# Touch_Drum_V1_Simple.net
KiCad netlist of a schematic drawn in EAGLE
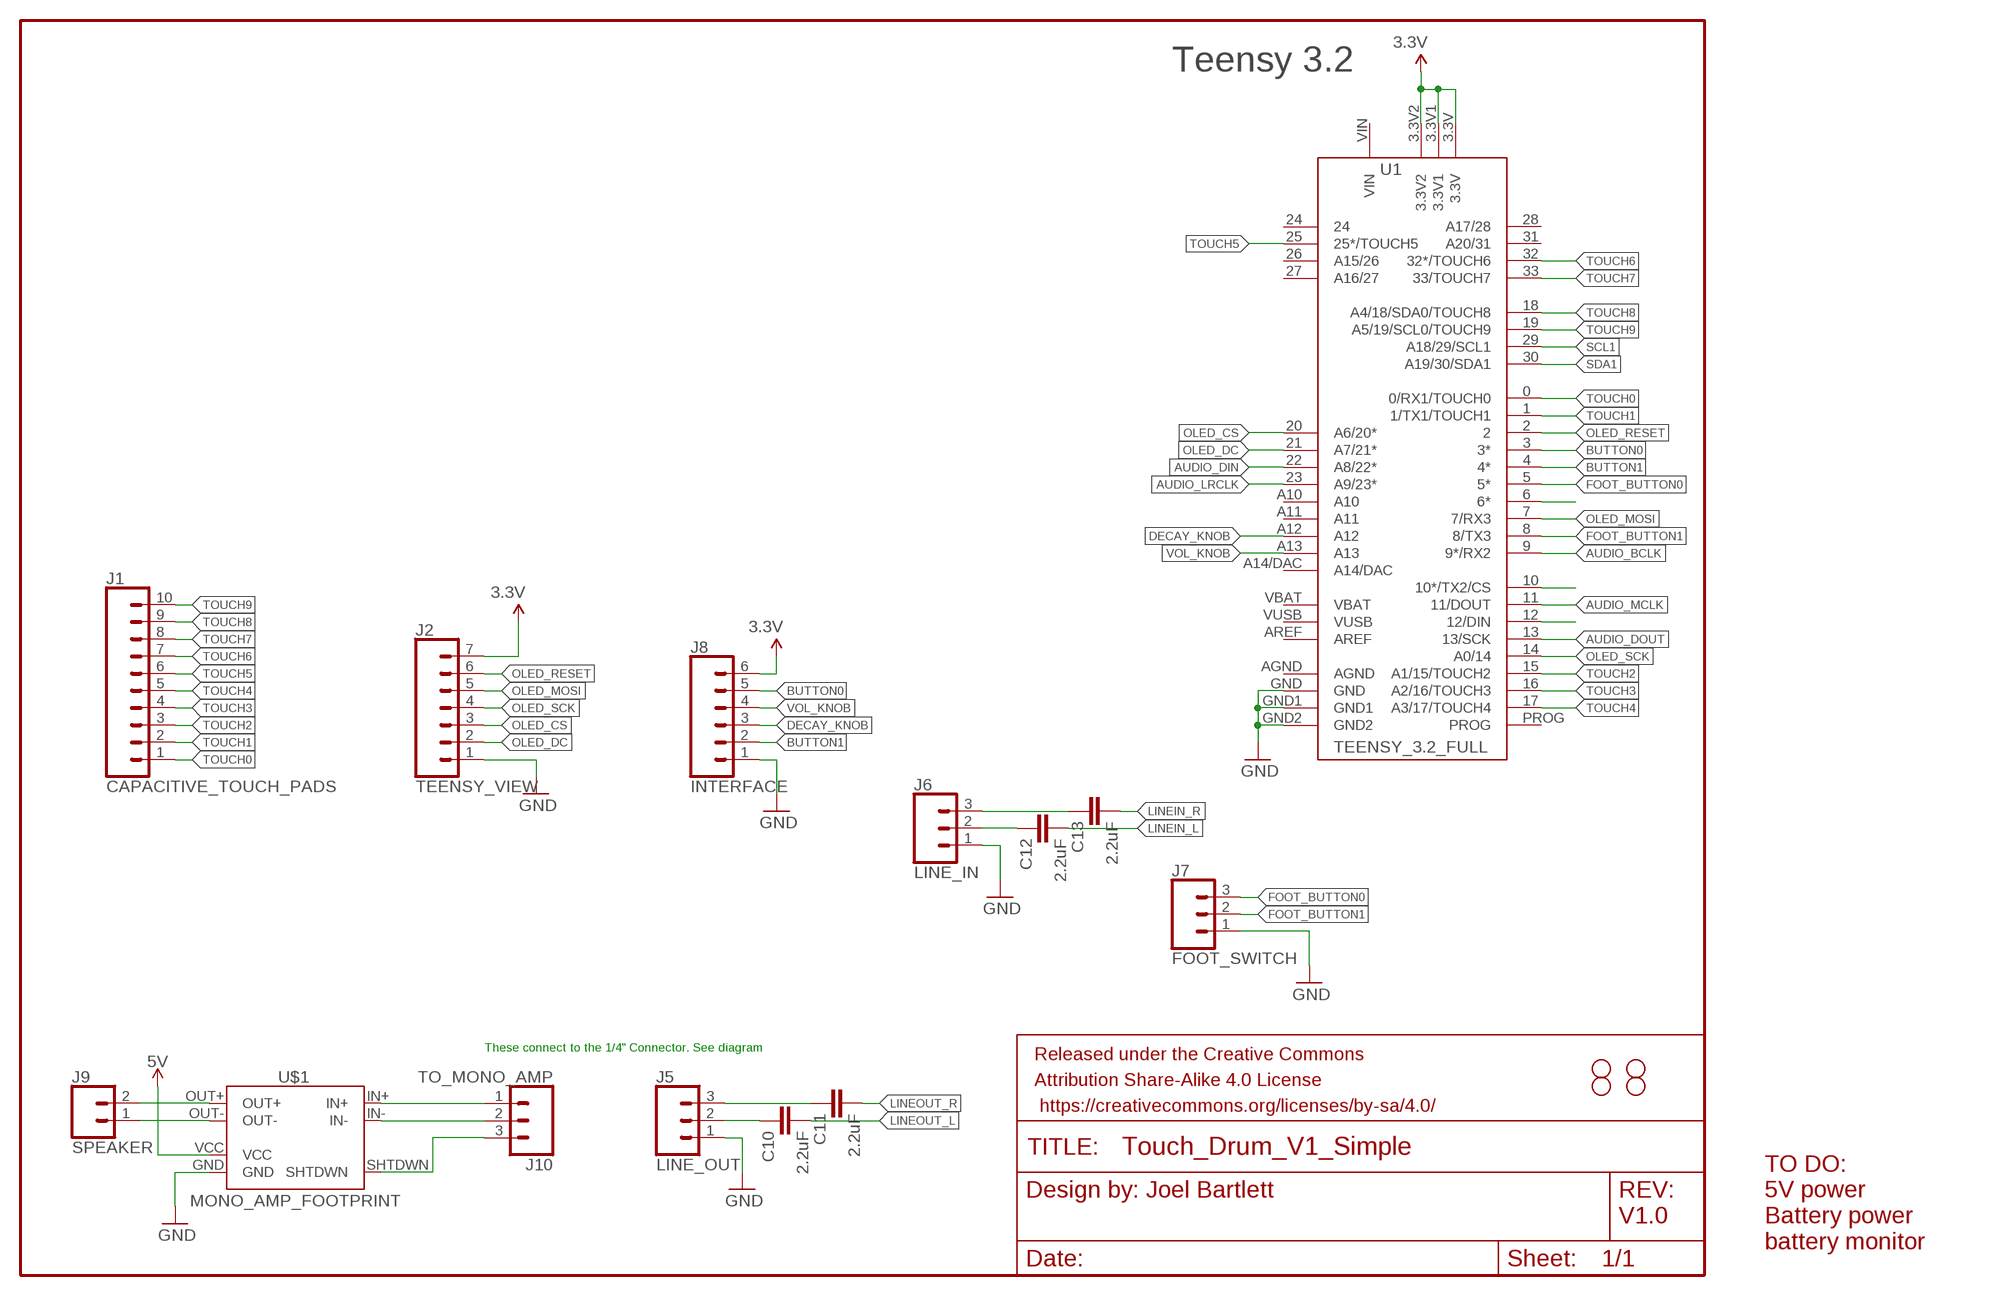
[diagram p0: schematic, sheet 1]

(export (version "E")
  (design (tool "Eeschema 10.0.6"))
  (components
    (comp (ref "C10")
      (value "2.2uF")
      (footprint "eagle-import:0603")
      (libsource (lib "eagle-import") (part "2.2UF-0603-10V-20%"))
    )
    (comp (ref "C11")
      (value "2.2uF")
      (footprint "eagle-import:0603")
      (libsource (lib "eagle-import") (part "2.2UF-0603-10V-20%"))
    )
    (comp (ref "C12")
      (value "2.2uF")
      (footprint "eagle-import:0603")
      (libsource (lib "eagle-import") (part "2.2UF-0603-10V-20%"))
    )
    (comp (ref "C13")
      (value "2.2uF")
      (footprint "eagle-import:0603")
      (libsource (lib "eagle-import") (part "2.2UF-0603-10V-20%"))
    )
    (comp (ref "FRAME1")
      (value "FRAME-LETTER")
      (footprint "eagle-import:CREATIVE_COMMONS")
      (libsource (lib "eagle-import") (part "FRAME-LETTER"))
    )
    (comp (ref "H1")
      (value "STAND-OFF")
      (footprint "eagle-import:STAND-OFF")
      (libsource (lib "eagle-import") (part "STAND-OFF"))
    )
    (comp (ref "H2")
      (value "STAND-OFF")
      (footprint "eagle-import:STAND-OFF")
      (libsource (lib "eagle-import") (part "STAND-OFF"))
    )
    (comp (ref "H3")
      (value "STAND-OFF")
      (footprint "eagle-import:STAND-OFF")
      (libsource (lib "eagle-import") (part "STAND-OFF"))
    )
    (comp (ref "H4")
      (value "STAND-OFF")
      (footprint "eagle-import:STAND-OFF")
      (libsource (lib "eagle-import") (part "STAND-OFF"))
    )
    (comp (ref "J1")
      (value "CAPACITIVE_TOUCH_PADS")
      (footprint "eagle-import:1X10_NO_SILK")
      (libsource (lib "eagle-import") (part "CONN_10NO_SILK_PTH_FEMALE"))
    )
    (comp (ref "J2")
      (value "TEENSY_VIEW")
      (footprint "eagle-import:1X07_NO_SILK")
      (libsource (lib "eagle-import") (part "CONN_07NO_SILK"))
    )
    (comp (ref "J5")
      (value "LINE_OUT")
      (footprint "eagle-import:1X03")
      (libsource (lib "eagle-import") (part "CONN_03"))
    )
    (comp (ref "J6")
      (value "LINE_IN")
      (footprint "eagle-import:1X03")
      (libsource (lib "eagle-import") (part "CONN_03"))
    )
    (comp (ref "J7")
      (value "FOOT_SWITCH")
      (footprint "eagle-import:1X03")
      (libsource (lib "eagle-import") (part "CONN_03"))
    )
    (comp (ref "J8")
      (value "INTERFACE")
      (footprint "eagle-import:1X06")
      (libsource (lib "eagle-import") (part "CONN_06SILK_FEMALE_PTH"))
    )
    (comp (ref "J9")
      (value "SPEAKER")
      (footprint "eagle-import:1X02")
      (libsource (lib "eagle-import") (part "CONN_02"))
    )
    (comp (ref "J10")
      (value "TO_MONO_AMP")
      (footprint "eagle-import:1X03")
      (libsource (lib "eagle-import") (part "CONN_03"))
    )
    (comp (ref "U$1")
      (value "MONO_AMP_FOOTPRINT")
      (footprint "eagle-import:MONO_AMP_FOOTPRINT")
      (libsource (lib "eagle-import") (part "MONO_AMP_FOOTPRINT"))
    )
    (comp (ref "U1")
      (value "TEENSY_3.2_FULL")
      (footprint "eagle-import:TEENSY_3.2_FULL")
      (libsource (lib "eagle-import") (part "TEENSY_3.2_FULL"))
    )
  )
  (nets
    (net (code "1") (name "3.3V") (class "Default")
      (node (ref "J2") (pin "7") (pinfunction "7_7") (pintype "passive"))
      (node (ref "J8") (pin "6") (pinfunction "6_6") (pintype "passive"))
      (node (ref "U1") (pin "3.3V") (pinfunction "3.3V_3.3V") (pintype "bidirectional"))
      (node (ref "U1") (pin "3.3V1") (pinfunction "3.3V1_3.3V1") (pintype "bidirectional"))
      (node (ref "U1") (pin "3.3V2") (pinfunction "3.3V2_3.3V2") (pintype "bidirectional"))
    )
    (net (code "2") (name "5V") (class "Default")
      (node (ref "U$1") (pin "VCC") (pinfunction "VCC_VCC") (pintype "bidirectional"))
    )
    (net (code "3") (name "AUDIO_BCLK") (class "Default")
      (node (ref "U1") (pin "9") (pinfunction "9*/RX2_9") (pintype "bidirectional"))
    )
    (net (code "4") (name "AUDIO_DIN") (class "Default")
      (node (ref "U1") (pin "22") (pinfunction "A8/22*_22") (pintype "bidirectional"))
    )
    (net (code "5") (name "AUDIO_DOUT") (class "Default")
      (node (ref "U1") (pin "13") (pinfunction "13/SCK_13") (pintype "bidirectional"))
    )
    (net (code "6") (name "AUDIO_LRCLK") (class "Default")
      (node (ref "U1") (pin "23") (pinfunction "A9/23*_23") (pintype "bidirectional"))
    )
    (net (code "7") (name "AUDIO_MCLK") (class "Default")
      (node (ref "U1") (pin "11") (pinfunction "11/DOUT_11") (pintype "bidirectional"))
    )
    (net (code "8") (name "BUTTON0") (class "Default")
      (node (ref "J8") (pin "5") (pinfunction "5_5") (pintype "passive"))
      (node (ref "U1") (pin "3") (pinfunction "3*_3") (pintype "bidirectional"))
    )
    (net (code "9") (name "BUTTON1") (class "Default")
      (node (ref "J8") (pin "2") (pinfunction "2_2") (pintype "passive"))
      (node (ref "U1") (pin "4") (pinfunction "4*_4") (pintype "bidirectional"))
    )
    (net (code "10") (name "DECAY_KNOB") (class "Default")
      (node (ref "J8") (pin "3") (pinfunction "3_3") (pintype "passive"))
      (node (ref "U1") (pin "A12") (pinfunction "A12_A12") (pintype "bidirectional"))
    )
    (net (code "11") (name "FOOT_BUTTON0") (class "Default")
      (node (ref "J7") (pin "3") (pinfunction "3_3") (pintype "passive"))
      (node (ref "U1") (pin "5") (pinfunction "5*_5") (pintype "bidirectional"))
    )
    (net (code "12") (name "FOOT_BUTTON1") (class "Default")
      (node (ref "J7") (pin "2") (pinfunction "2_2") (pintype "passive"))
      (node (ref "U1") (pin "8") (pinfunction "8/TX3_8") (pintype "bidirectional"))
    )
    (net (code "13") (name "GND") (class "Default")
      (node (ref "J2") (pin "1") (pinfunction "1_1") (pintype "passive"))
      (node (ref "J5") (pin "1") (pinfunction "1_1") (pintype "passive"))
      (node (ref "J6") (pin "1") (pinfunction "1_1") (pintype "passive"))
      (node (ref "J7") (pin "1") (pinfunction "1_1") (pintype "passive"))
      (node (ref "J8") (pin "1") (pinfunction "1_1") (pintype "passive"))
      (node (ref "U$1") (pin "GND") (pinfunction "GND_GND") (pintype "bidirectional"))
      (node (ref "U1") (pin "GND") (pinfunction "GND_GND") (pintype "bidirectional"))
      (node (ref "U1") (pin "GND1") (pinfunction "GND1_GND1") (pintype "bidirectional"))
      (node (ref "U1") (pin "GND2") (pinfunction "GND2_GND2") (pintype "bidirectional"))
    )
    (net (code "14") (name "LINEIN_L") (class "Default")
      (node (ref "C12") (pin "2") (pinfunction "2_2") (pintype "passive"))
    )
    (net (code "15") (name "LINEIN_R") (class "Default")
      (node (ref "C13") (pin "2") (pinfunction "2_2") (pintype "passive"))
    )
    (net (code "16") (name "LINEOUT_L") (class "Default")
      (node (ref "C10") (pin "2") (pinfunction "2_2") (pintype "passive"))
    )
    (net (code "17") (name "LINEOUT_R") (class "Default")
      (node (ref "C11") (pin "2") (pinfunction "2_2") (pintype "passive"))
    )
    (net (code "18") (name "Net-(C10-Pad1)") (class "Default")
      (node (ref "C10") (pin "1") (pinfunction "1_1") (pintype "passive"))
      (node (ref "J5") (pin "2") (pinfunction "2_2") (pintype "passive"))
    )
    (net (code "19") (name "Net-(C11-Pad1)") (class "Default")
      (node (ref "C11") (pin "1") (pinfunction "1_1") (pintype "passive"))
      (node (ref "J5") (pin "3") (pinfunction "3_3") (pintype "passive"))
    )
    (net (code "20") (name "Net-(C12-Pad1)") (class "Default")
      (node (ref "C12") (pin "1") (pinfunction "1_1") (pintype "passive"))
      (node (ref "J6") (pin "2") (pinfunction "2_2") (pintype "passive"))
    )
    (net (code "21") (name "Net-(C13-Pad1)") (class "Default")
      (node (ref "C13") (pin "1") (pinfunction "1_1") (pintype "passive"))
      (node (ref "J6") (pin "3") (pinfunction "3_3") (pintype "passive"))
    )
    (net (code "22") (name "Net-(J9-Pad1)") (class "Default")
      (node (ref "J9") (pin "1") (pinfunction "1_1") (pintype "passive"))
      (node (ref "U$1") (pin "OUT-") (pinfunction "OUT-_OUT-") (pintype "bidirectional"))
    )
    (net (code "23") (name "Net-(J9-Pad2)") (class "Default")
      (node (ref "J9") (pin "2") (pinfunction "2_2") (pintype "passive"))
      (node (ref "U$1") (pin "OUT+") (pinfunction "OUT+_OUT+") (pintype "bidirectional"))
    )
    (net (code "24") (name "Net-(J10-Pad1)") (class "Default")
      (node (ref "J10") (pin "1") (pinfunction "1_1") (pintype "passive"))
      (node (ref "U$1") (pin "IN+") (pinfunction "IN+_IN+") (pintype "bidirectional"))
    )
    (net (code "25") (name "Net-(J10-Pad2)") (class "Default")
      (node (ref "J10") (pin "2") (pinfunction "2_2") (pintype "passive"))
      (node (ref "U$1") (pin "IN-") (pinfunction "IN-_IN-") (pintype "bidirectional"))
    )
    (net (code "26") (name "Net-(J10-Pad3)") (class "Default")
      (node (ref "J10") (pin "3") (pinfunction "3_3") (pintype "passive"))
      (node (ref "U$1") (pin "SHTDWN") (pinfunction "SHTDWN_SHTDWN") (pintype "bidirectional"))
    )
    (net (code "27") (name "OLED_CS") (class "Default")
      (node (ref "J2") (pin "3") (pinfunction "3_3") (pintype "passive"))
      (node (ref "U1") (pin "20") (pinfunction "A6/20*_20") (pintype "bidirectional"))
    )
    (net (code "28") (name "OLED_DC") (class "Default")
      (node (ref "J2") (pin "2") (pinfunction "2_2") (pintype "passive"))
      (node (ref "U1") (pin "21") (pinfunction "A7/21*_21") (pintype "bidirectional"))
    )
    (net (code "29") (name "OLED_MOSI") (class "Default")
      (node (ref "J2") (pin "5") (pinfunction "5_5") (pintype "passive"))
      (node (ref "U1") (pin "7") (pinfunction "7/RX3_7") (pintype "bidirectional"))
    )
    (net (code "30") (name "OLED_RESET") (class "Default")
      (node (ref "J2") (pin "6") (pinfunction "6_6") (pintype "passive"))
      (node (ref "U1") (pin "2") (pinfunction "2_2") (pintype "bidirectional"))
    )
    (net (code "31") (name "OLED_SCK") (class "Default")
      (node (ref "J2") (pin "4") (pinfunction "4_4") (pintype "passive"))
      (node (ref "U1") (pin "14") (pinfunction "A0/14_14") (pintype "bidirectional"))
    )
    (net (code "32") (name "SCL1") (class "Default")
      (node (ref "U1") (pin "29") (pinfunction "A18/29/SCL1_29") (pintype "bidirectional"))
    )
    (net (code "33") (name "SDA1") (class "Default")
      (node (ref "U1") (pin "30") (pinfunction "A19/30/SDA1_30") (pintype "bidirectional"))
    )
    (net (code "34") (name "TOUCH0") (class "Default")
      (node (ref "J1") (pin "1") (pinfunction "1_1") (pintype "passive"))
      (node (ref "U1") (pin "0") (pinfunction "0/RX1/TOUCH0_0") (pintype "bidirectional"))
    )
    (net (code "35") (name "TOUCH1") (class "Default")
      (node (ref "J1") (pin "2") (pinfunction "2_2") (pintype "passive"))
      (node (ref "U1") (pin "1") (pinfunction "1/TX1/TOUCH1_1") (pintype "bidirectional"))
    )
    (net (code "36") (name "TOUCH2") (class "Default")
      (node (ref "J1") (pin "3") (pinfunction "3_3") (pintype "passive"))
      (node (ref "U1") (pin "15") (pinfunction "A1/15/TOUCH2_15") (pintype "bidirectional"))
    )
    (net (code "37") (name "TOUCH3") (class "Default")
      (node (ref "J1") (pin "4") (pinfunction "4_4") (pintype "passive"))
      (node (ref "U1") (pin "16") (pinfunction "A2/16/TOUCH3_16") (pintype "bidirectional"))
    )
    (net (code "38") (name "TOUCH4") (class "Default")
      (node (ref "J1") (pin "5") (pinfunction "5_5") (pintype "passive"))
      (node (ref "U1") (pin "17") (pinfunction "A3/17/TOUCH4_17") (pintype "bidirectional"))
    )
    (net (code "39") (name "TOUCH5") (class "Default")
      (node (ref "J1") (pin "6") (pinfunction "6_6") (pintype "passive"))
      (node (ref "U1") (pin "25") (pinfunction "25*/TOUCH5_25") (pintype "bidirectional"))
    )
    (net (code "40") (name "TOUCH6") (class "Default")
      (node (ref "J1") (pin "7") (pinfunction "7_7") (pintype "passive"))
      (node (ref "U1") (pin "32") (pinfunction "32*/TOUCH6_32") (pintype "bidirectional"))
    )
    (net (code "41") (name "TOUCH7") (class "Default")
      (node (ref "J1") (pin "8") (pinfunction "8_8") (pintype "passive"))
      (node (ref "U1") (pin "33") (pinfunction "33/TOUCH7_33") (pintype "bidirectional"))
    )
    (net (code "42") (name "TOUCH8") (class "Default")
      (node (ref "J1") (pin "9") (pinfunction "9_9") (pintype "passive"))
      (node (ref "U1") (pin "18") (pinfunction "A4/18/SDA0/TOUCH8_18") (pintype "bidirectional"))
    )
    (net (code "43") (name "TOUCH9") (class "Default")
      (node (ref "J1") (pin "10") (pinfunction "10_10") (pintype "passive"))
      (node (ref "U1") (pin "19") (pinfunction "A5/19/SCL0/TOUCH9_19") (pintype "bidirectional"))
    )
    (net (code "44") (name "VOL_KNOB") (class "Default")
      (node (ref "J8") (pin "4") (pinfunction "4_4") (pintype "passive"))
      (node (ref "U1") (pin "A13") (pinfunction "A13_A13") (pintype "bidirectional"))
    )
    (net (code "45") (name "unconnected-(U1-6*-Pad6)") (class "Default")
      (node (ref "U1") (pin "6") (pinfunction "6*_6") (pintype "bidirectional"))
    )
    (net (code "46") (name "unconnected-(U1-10*{slash}TX2{slash}CS-Pad10)") (class "Default")
      (node (ref "U1") (pin "10") (pinfunction "10*/TX2/CS_10") (pintype "bidirectional"))
    )
    (net (code "47") (name "unconnected-(U1-12{slash}DIN-Pad12)") (class "Default")
      (node (ref "U1") (pin "12") (pinfunction "12/DIN_12") (pintype "bidirectional"))
    )
    (net (code "48") (name "unconnected-(U1-A15{slash}26-Pad26)") (class "Default")
      (node (ref "U1") (pin "26") (pinfunction "A15/26_26") (pintype "bidirectional"))
    )
    (net (code "49") (name "unconnected-(U1-A16{slash}27-Pad27)") (class "Default")
      (node (ref "U1") (pin "27") (pinfunction "A16/27_27") (pintype "bidirectional"))
    )
    (net (code "50") (name "unconnected-(U1-A17{slash}28-Pad28)") (class "Default")
      (node (ref "U1") (pin "28") (pinfunction "A17/28_28") (pintype "bidirectional"))
    )
    (net (code "51") (name "unconnected-(U1-A20{slash}31-Pad31)") (class "Default")
      (node (ref "U1") (pin "31") (pinfunction "A20/31_31") (pintype "bidirectional"))
    )
    (net (code "52") (name "unconnected-(U1-Pad24)") (class "Default")
      (node (ref "U1") (pin "24") (pinfunction "24_24") (pintype "bidirectional"))
    )
    (net (code "53") (name "unconnected-(U1-PadA10)") (class "Default")
      (node (ref "U1") (pin "A10") (pinfunction "A10_A10") (pintype "bidirectional"))
    )
    (net (code "54") (name "unconnected-(U1-PadA11)") (class "Default")
      (node (ref "U1") (pin "A11") (pinfunction "A11_A11") (pintype "bidirectional"))
    )
    (net (code "55") (name "unconnected-(U1-PadA14{slash}DAC)") (class "Default")
      (node (ref "U1") (pin "A14/DAC") (pinfunction "A14/DAC_A14/DAC") (pintype "bidirectional"))
    )
    (net (code "56") (name "unconnected-(U1-PadAGND)") (class "Default")
      (node (ref "U1") (pin "AGND") (pinfunction "AGND_AGND") (pintype "bidirectional"))
    )
    (net (code "57") (name "unconnected-(U1-PadAREF)") (class "Default")
      (node (ref "U1") (pin "AREF") (pinfunction "AREF_AREF") (pintype "bidirectional"))
    )
    (net (code "58") (name "unconnected-(U1-PadPROG)") (class "Default")
      (node (ref "U1") (pin "PROG") (pinfunction "PROG_PROG") (pintype "bidirectional"))
    )
    (net (code "59") (name "unconnected-(U1-PadVBAT)") (class "Default")
      (node (ref "U1") (pin "VBAT") (pinfunction "VBAT_VBAT") (pintype "bidirectional"))
    )
    (net (code "60") (name "unconnected-(U1-PadVIN)") (class "Default")
      (node (ref "U1") (pin "VIN") (pinfunction "VIN_VIN") (pintype "bidirectional"))
    )
    (net (code "61") (name "unconnected-(U1-PadVUSB)") (class "Default")
      (node (ref "U1") (pin "VUSB") (pinfunction "VUSB_VUSB") (pintype "bidirectional"))
    )
  )
)
